# Supplies01.net
KiCad netlist of a schematic drawn in Altium Designer
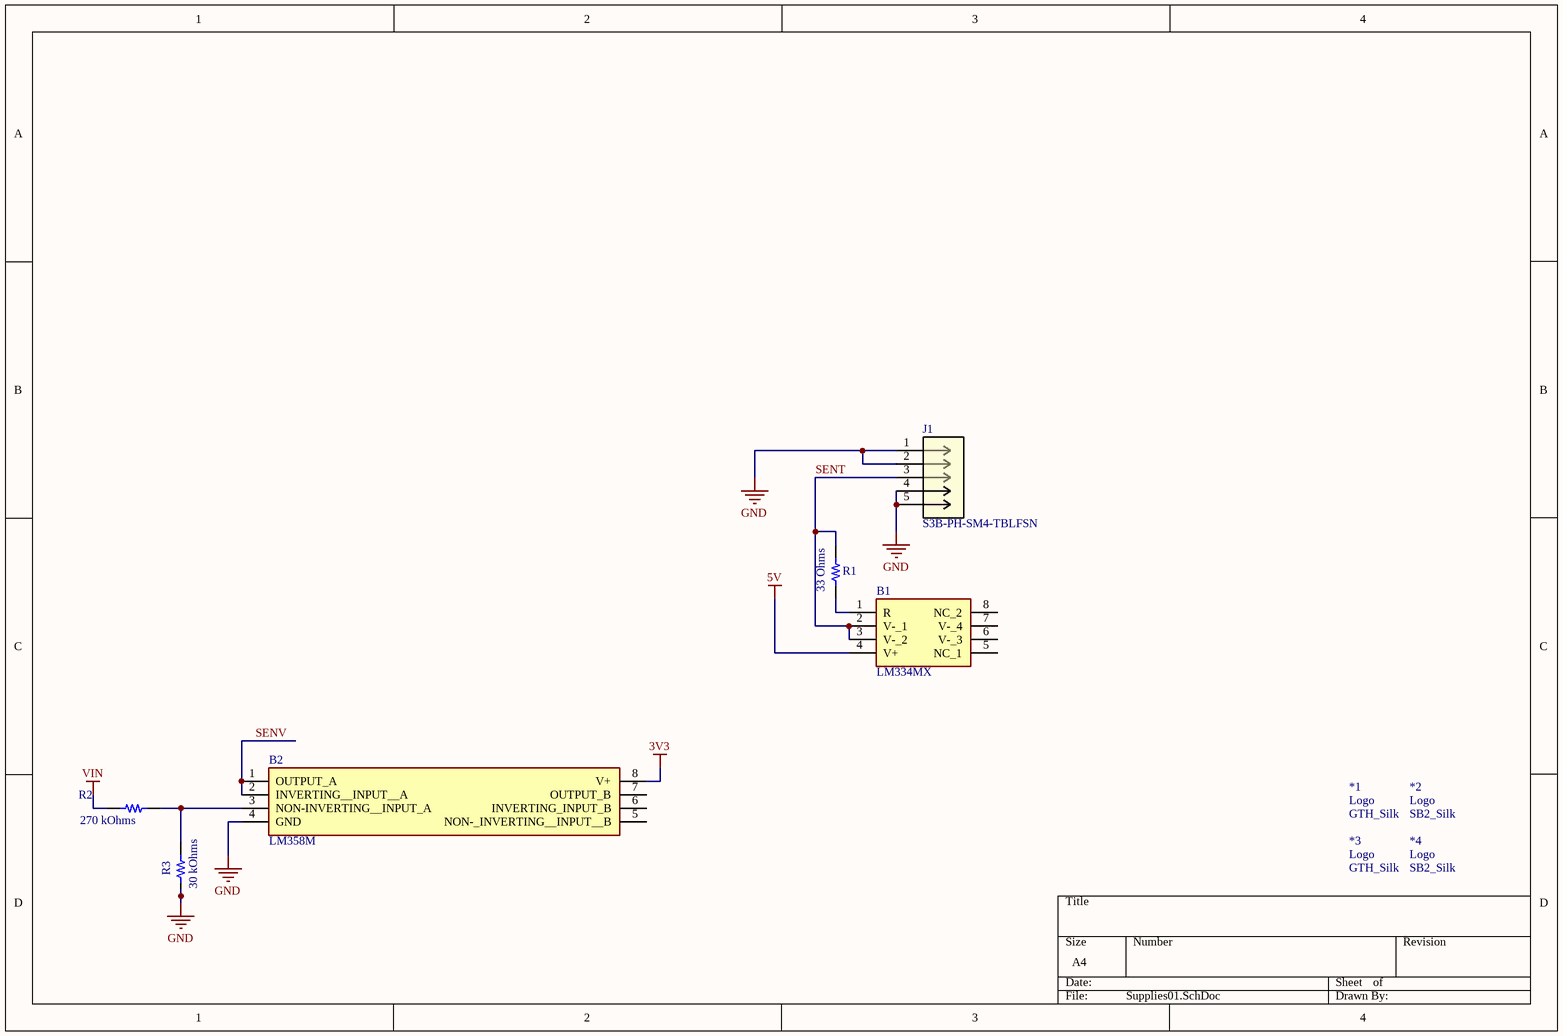
[diagram p0: Supplies01.SchDoc]

(export (version "E")
  (design (tool "Eeschema 10.0.6"))
  (components
    (comp (ref "*1")
      (value "GTH_Silk")
      (footprint "TECHHUB_SILK")
      (libsource (lib "LogoGIBIC") (part "GTH_Silk"))
    )
    (comp (ref "*2")
      (value "SB2_Silk")
      (footprint "SMARTBEDDING2_SILK")
      (libsource (lib "LogoGIBIC") (part "SB2_Silk"))
    )
    (comp (ref "*3")
      (value "GTH_Silk")
      (footprint "TECHHUB_SILK")
      (libsource (lib "LogoGIBIC") (part "GTH_Silk"))
    )
    (comp (ref "*4")
      (value "SB2_Silk")
      (footprint "SMARTBEDDING2_SILK")
      (libsource (lib "LogoGIBIC") (part "SB2_Silk"))
    )
    (comp (ref "B1")
      (value "LM334MX")
      (footprint "SOIC127P600X175-8N")
      (description "Current & Power Monitors & Regulators 3-Terminal Adjustable Current Source 8-SOIC 0 to 70")
      (fields (field (name "MOUSER PART NUMBER") "926-LM334MX"))
      (libsource (lib "LM334MX") (part "LM334MX"))
    )
    (comp (ref "B2")
      (value "LM358M")
      (footprint "SOIC127P600X175-8N")
      (description "Low Power Dual Operational Amplifiers")
      (fields (field (name "MOUSER PART NUMBER") "926-LM358M"))
      (libsource (lib "LM358M") (part "LM358M"))
    )
    (comp (ref "J1")
      (value "S3B-PH-SM4-TBLFSN")
      (footprint "CONN_S3B-PH-SM4-TBLFSN_JST")
      (description "No Description Available")
      (libsource (lib "S3B-PH-SM4-TBLFSN") (part "S3B-PH-SM4-TBLFSN"))
    )
    (comp (ref "R1")
      (value "33 Ohms")
      (footprint "YAGEO RES 0603_1608")
      (description "RES 33 OHM 5% 1/10W 0603")
      (fields (field (name "TOLERANCE") "±5%") (field (name "PART NUMBER") "RC0603JR-0733RL"))
      (libsource (lib "Celestial Altium Library - altium_library") (part "Resistor"))
    )
    (comp (ref "R2")
      (value "270 kOhms")
      (footprint "YAGEO RES 0603_1608")
      (description "RES 270K OHM 1% 1/10W 0603")
      (fields (field (name "TOLERANCE") "±1%") (field (name "PART NUMBER") "RC0603FR-07270KL"))
      (libsource (lib "Celestial Altium Library - altium_library") (part "Resistor"))
    )
    (comp (ref "R3")
      (value "30 kOhms")
      (footprint "YAGEO RES 0603_1608")
      (description "RES SMD 30K OHM 1% 1/10W 0603")
      (fields (field (name "TOLERANCE") "±1%") (field (name "PART NUMBER") "AC0603FR-0730KL"))
      (libsource (lib "Celestial Altium Library - altium_library") (part "Resistor"))
    )
  )
  (nets
    (net (code "1") (name "/SENT") (class "Default")
      (node (ref "B1") (pin "2") (pinfunction "V-_1_2") (pintype "passive"))
      (node (ref "B1") (pin "3") (pinfunction "V-_2_3") (pintype "passive"))
      (node (ref "J1") (pin "3") (pinfunction "3_3") (pintype "passive"))
      (node (ref "R1") (pin "1") (pinfunction "1_1") (pintype "passive"))
    )
    (net (code "2") (name "/SENV") (class "Default")
      (node (ref "B2") (pin "1") (pinfunction "OUTPUT_A_1") (pintype "passive"))
      (node (ref "B2") (pin "2") (pinfunction "INVERTING__INPUT__A_2") (pintype "passive"))
    )
    (net (code "3") (name "3V3") (class "Default")
      (node (ref "B2") (pin "8") (pinfunction "V+_8") (pintype "passive"))
    )
    (net (code "4") (name "5V") (class "Default")
      (node (ref "B1") (pin "4") (pinfunction "V+_4") (pintype "passive"))
    )
    (net (code "5") (name "GND") (class "Default")
      (node (ref "B2") (pin "4") (pinfunction "GND_4") (pintype "passive"))
      (node (ref "J1") (pin "1") (pinfunction "1_1") (pintype "passive"))
      (node (ref "J1") (pin "2") (pinfunction "2_2") (pintype "passive"))
      (node (ref "J1") (pin "4") (pinfunction "4_4") (pintype "passive"))
      (node (ref "J1") (pin "5") (pinfunction "5_5") (pintype "passive"))
      (node (ref "R3") (pin "1") (pinfunction "1_1") (pintype "passive"))
    )
    (net (code "6") (name "Net-(B1-R)") (class "Default")
      (node (ref "B1") (pin "1") (pinfunction "R_1") (pintype "passive"))
      (node (ref "R1") (pin "2") (pinfunction "2_2") (pintype "passive"))
    )
    (net (code "7") (name "Net-(B2-NON-INVERTING__INPUT_A)") (class "Default")
      (node (ref "B2") (pin "3") (pinfunction "NON-INVERTING__INPUT_A_3") (pintype "passive"))
      (node (ref "R2") (pin "1") (pinfunction "1_1") (pintype "passive"))
      (node (ref "R3") (pin "2") (pinfunction "2_2") (pintype "passive"))
    )
    (net (code "8") (name "VIN") (class "Default")
      (node (ref "R2") (pin "2") (pinfunction "2_2") (pintype "passive"))
    )
    (net (code "9") (name "unconnected-(B1-NC_1-Pad5)") (class "Default")
      (node (ref "B1") (pin "5") (pinfunction "NC_1_5") (pintype "passive"))
    )
    (net (code "10") (name "unconnected-(B1-NC_2-Pad8)") (class "Default")
      (node (ref "B1") (pin "8") (pinfunction "NC_2_8") (pintype "passive"))
    )
    (net (code "11") (name "unconnected-(B1-V-_3-Pad6)") (class "Default")
      (node (ref "B1") (pin "6") (pinfunction "V-_3_6") (pintype "passive"))
    )
    (net (code "12") (name "unconnected-(B1-V-_4-Pad7)") (class "Default")
      (node (ref "B1") (pin "7") (pinfunction "V-_4_7") (pintype "passive"))
    )
    (net (code "13") (name "unconnected-(B2-INVERTING_INPUT_B-Pad6)") (class "Default")
      (node (ref "B2") (pin "6") (pinfunction "INVERTING_INPUT_B_6") (pintype "passive"))
    )
    (net (code "14") (name "unconnected-(B2-NON-_INVERTING__INPUT__B-Pad5)") (class "Default")
      (node (ref "B2") (pin "5") (pinfunction "NON-_INVERTING__INPUT__B_5") (pintype "passive"))
    )
    (net (code "15") (name "unconnected-(B2-OUTPUT_B-Pad7)") (class "Default")
      (node (ref "B2") (pin "7") (pinfunction "OUTPUT_B_7") (pintype "passive"))
    )
  )
)
